# TRHPSVG_Controls.net
KiCad netlist of a schematic drawn in EAGLE
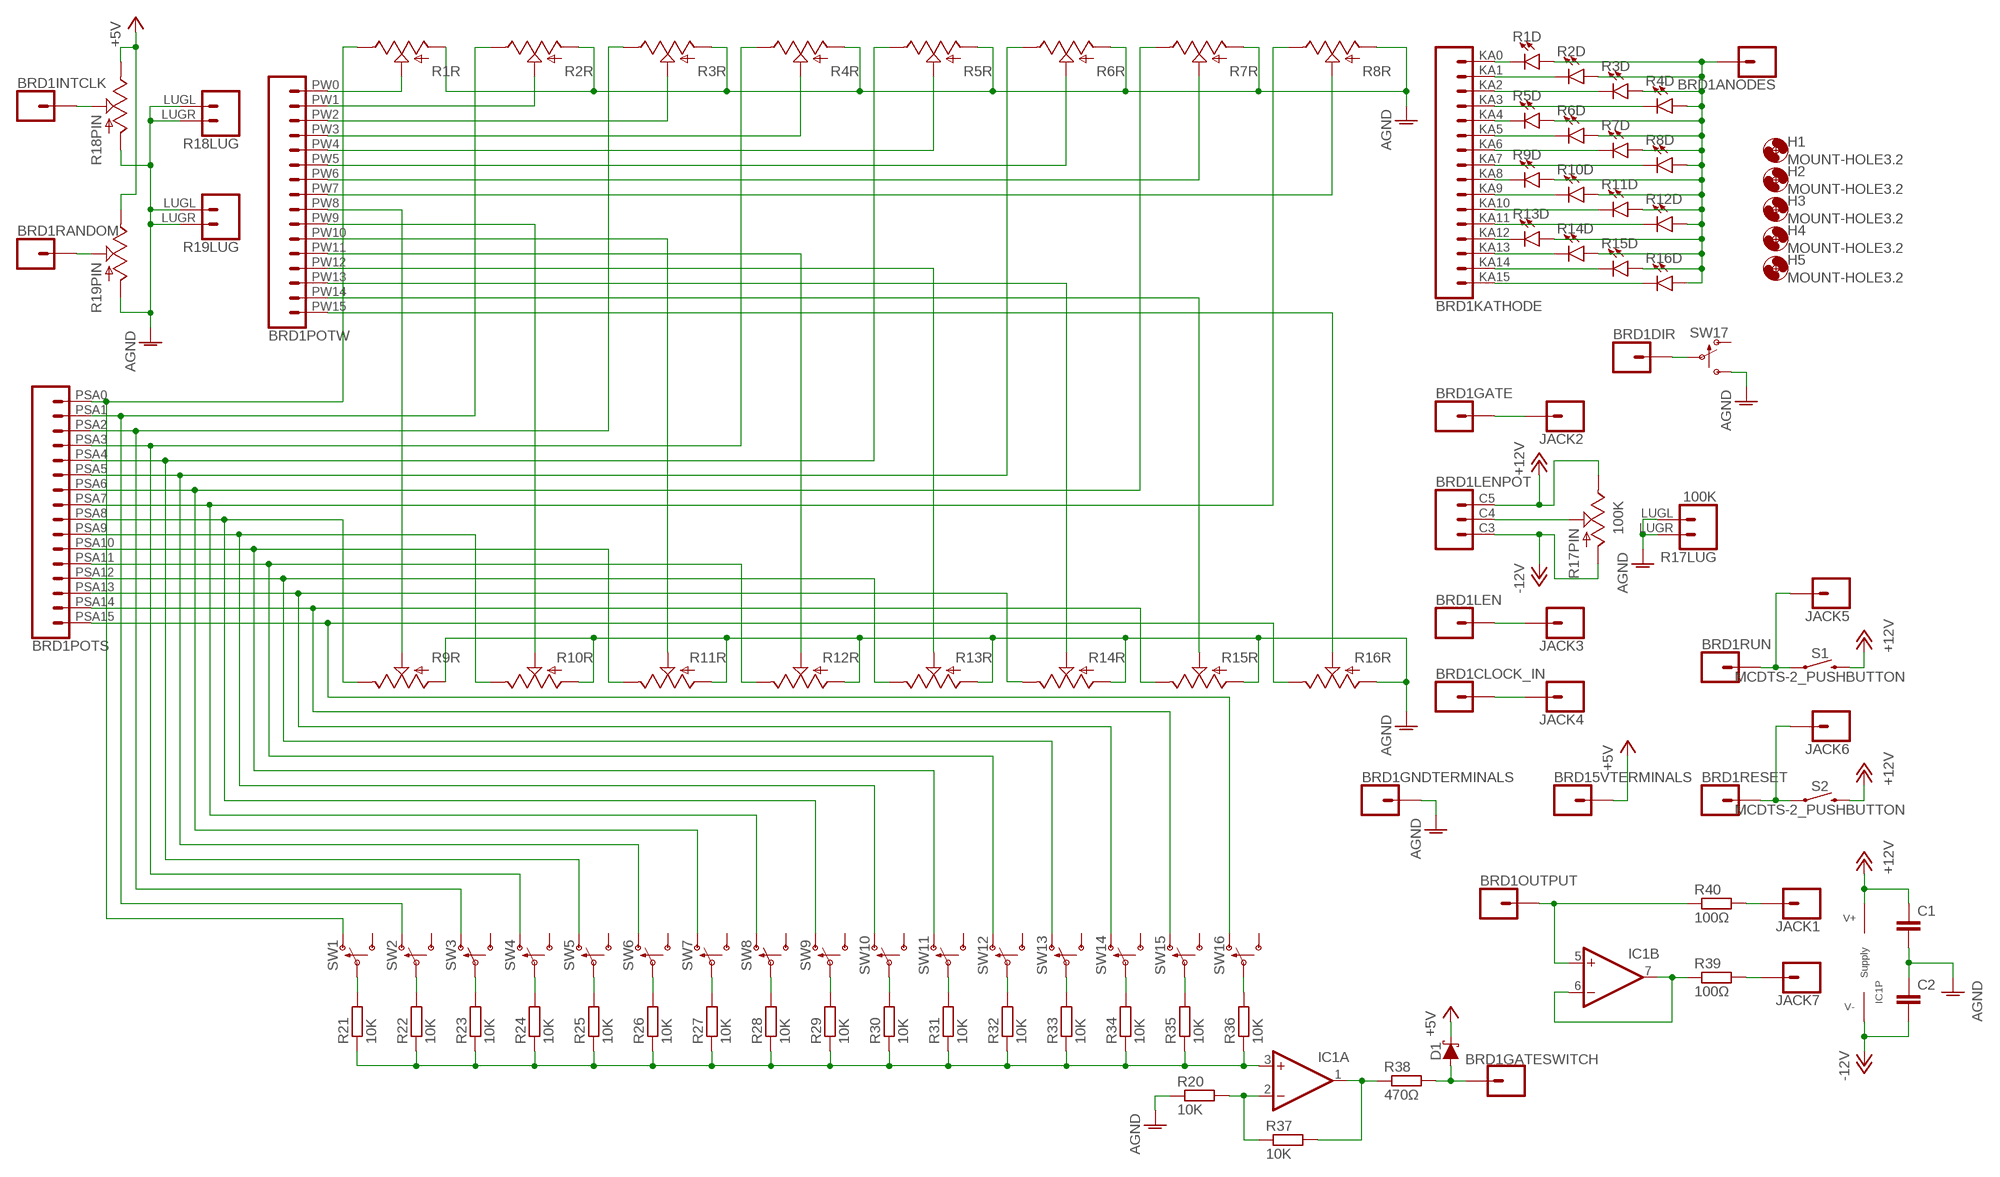
[diagram p0: schematic, sheet 1]

(export (version "E")
  (design (tool "Eeschema 10.0.6"))
  (components
    (comp (ref "BRD1")
      (value "TRHPSVG_LINK")
      (footprint "eagle-import:TRHPSVG")
      (libsource (lib "eagle-import") (part "TRHPSVG_LINK"))
    )
    (comp (ref "C1")
      (value "C-EU050-025X075")
      (footprint "eagle-import:C050-025X075")
      (libsource (lib "eagle-import") (part "C-EU050-025X075"))
    )
    (comp (ref "C2")
      (value "C-EU050-025X075")
      (footprint "eagle-import:C050-025X075")
      (libsource (lib "eagle-import") (part "C-EU050-025X075"))
    )
    (comp (ref "D1")
      (value "SCHOTTKY_DO35")
      (footprint "eagle-import:DO35-7")
      (libsource (lib "eagle-import") (part "SCHOTTKY_DO35"))
    )
    (comp (ref "H1")
      (value "MOUNT-HOLE3.2")
      (footprint "eagle-import:3,2")
      (libsource (lib "eagle-import") (part "MOUNT-HOLE3.2"))
    )
    (comp (ref "H2")
      (value "MOUNT-HOLE3.2")
      (footprint "eagle-import:3,2")
      (libsource (lib "eagle-import") (part "MOUNT-HOLE3.2"))
    )
    (comp (ref "H3")
      (value "MOUNT-HOLE3.2")
      (footprint "eagle-import:3,2")
      (libsource (lib "eagle-import") (part "MOUNT-HOLE3.2"))
    )
    (comp (ref "H4")
      (value "MOUNT-HOLE3.2")
      (footprint "eagle-import:3,2")
      (libsource (lib "eagle-import") (part "MOUNT-HOLE3.2"))
    )
    (comp (ref "H5")
      (value "MOUNT-HOLE3.2")
      (footprint "eagle-import:3,2")
      (libsource (lib "eagle-import") (part "MOUNT-HOLE3.2"))
    )
    (comp (ref "IC1")
      (value "TL0X2DIL")
      (footprint "eagle-import:DIL08")
      (libsource (lib "eagle-import") (part "TL0X2DIL"))
    )
    (comp (ref "JACK1")
      (value "1XWIREPAD")
      (footprint "eagle-import:1X01")
      (libsource (lib "eagle-import") (part "1XWIREPAD"))
    )
    (comp (ref "JACK2")
      (value "1XWIREPAD")
      (footprint "eagle-import:1X01")
      (libsource (lib "eagle-import") (part "1XWIREPAD"))
    )
    (comp (ref "JACK3")
      (value "1XWIREPAD")
      (footprint "eagle-import:1X01")
      (libsource (lib "eagle-import") (part "1XWIREPAD"))
    )
    (comp (ref "JACK4")
      (value "1XWIREPAD")
      (footprint "eagle-import:1X01")
      (libsource (lib "eagle-import") (part "1XWIREPAD"))
    )
    (comp (ref "JACK5")
      (value "1XWIREPAD")
      (footprint "eagle-import:1X01")
      (libsource (lib "eagle-import") (part "1XWIREPAD"))
    )
    (comp (ref "JACK6")
      (value "1XWIREPAD")
      (footprint "eagle-import:1X01")
      (libsource (lib "eagle-import") (part "1XWIREPAD"))
    )
    (comp (ref "JACK7")
      (value "1XWIREPAD")
      (footprint "eagle-import:1X01")
      (libsource (lib "eagle-import") (part "1XWIREPAD"))
    )
    (comp (ref "R1")
      (value "PTL30_SLIDER")
      (footprint "eagle-import:LEDSLIDER45MM")
      (libsource (lib "eagle-import") (part "PTL30_SLIDER"))
    )
    (comp (ref "R2")
      (value "PTL30_SLIDER")
      (footprint "eagle-import:LEDSLIDER45MM")
      (libsource (lib "eagle-import") (part "PTL30_SLIDER"))
    )
    (comp (ref "R3")
      (value "PTL30_SLIDER")
      (footprint "eagle-import:LEDSLIDER45MM")
      (libsource (lib "eagle-import") (part "PTL30_SLIDER"))
    )
    (comp (ref "R4")
      (value "PTL30_SLIDER")
      (footprint "eagle-import:LEDSLIDER45MM")
      (libsource (lib "eagle-import") (part "PTL30_SLIDER"))
    )
    (comp (ref "R5")
      (value "PTL30_SLIDER")
      (footprint "eagle-import:LEDSLIDER45MM")
      (libsource (lib "eagle-import") (part "PTL30_SLIDER"))
    )
    (comp (ref "R6")
      (value "PTL30_SLIDER")
      (footprint "eagle-import:LEDSLIDER45MM")
      (libsource (lib "eagle-import") (part "PTL30_SLIDER"))
    )
    (comp (ref "R7")
      (value "PTL30_SLIDER")
      (footprint "eagle-import:LEDSLIDER45MM")
      (libsource (lib "eagle-import") (part "PTL30_SLIDER"))
    )
    (comp (ref "R8")
      (value "PTL30_SLIDER")
      (footprint "eagle-import:LEDSLIDER45MM")
      (libsource (lib "eagle-import") (part "PTL30_SLIDER"))
    )
    (comp (ref "R9")
      (value "PTL30_SLIDER")
      (footprint "eagle-import:LEDSLIDER45MM")
      (libsource (lib "eagle-import") (part "PTL30_SLIDER"))
    )
    (comp (ref "R10")
      (value "PTL30_SLIDER")
      (footprint "eagle-import:LEDSLIDER45MM")
      (libsource (lib "eagle-import") (part "PTL30_SLIDER"))
    )
    (comp (ref "R11")
      (value "PTL30_SLIDER")
      (footprint "eagle-import:LEDSLIDER45MM")
      (libsource (lib "eagle-import") (part "PTL30_SLIDER"))
    )
    (comp (ref "R12")
      (value "PTL30_SLIDER")
      (footprint "eagle-import:LEDSLIDER45MM")
      (libsource (lib "eagle-import") (part "PTL30_SLIDER"))
    )
    (comp (ref "R13")
      (value "PTL30_SLIDER")
      (footprint "eagle-import:LEDSLIDER45MM")
      (libsource (lib "eagle-import") (part "PTL30_SLIDER"))
    )
    (comp (ref "R14")
      (value "PTL30_SLIDER")
      (footprint "eagle-import:LEDSLIDER45MM")
      (libsource (lib "eagle-import") (part "PTL30_SLIDER"))
    )
    (comp (ref "R15")
      (value "PTL30_SLIDER")
      (footprint "eagle-import:LEDSLIDER45MM")
      (libsource (lib "eagle-import") (part "PTL30_SLIDER"))
    )
    (comp (ref "R16")
      (value "PTL30_SLIDER")
      (footprint "eagle-import:LEDSLIDER45MM")
      (libsource (lib "eagle-import") (part "PTL30_SLIDER"))
    )
    (comp (ref "R17")
      (value "100K")
      (footprint "eagle-import:ALPHA_RV09_9MMPOT")
      (libsource (lib "eagle-import") (part "POTENTIOMETER"))
    )
    (comp (ref "R18")
      (value "POTENTIOMETER")
      (footprint "eagle-import:ALPHA_RV09_9MMPOT")
      (libsource (lib "eagle-import") (part "POTENTIOMETER"))
    )
    (comp (ref "R19")
      (value "POTENTIOMETER")
      (footprint "eagle-import:ALPHA_RV09_9MMPOT")
      (libsource (lib "eagle-import") (part "POTENTIOMETER"))
    )
    (comp (ref "R20")
      (value "10K")
      (footprint "eagle-import:0207_10")
      (libsource (lib "eagle-import") (part "R-EU_0207/10"))
    )
    (comp (ref "R21")
      (value "10K")
      (footprint "eagle-import:0207_10")
      (libsource (lib "eagle-import") (part "R-EU_0207/10"))
    )
    (comp (ref "R22")
      (value "10K")
      (footprint "eagle-import:0207_10")
      (libsource (lib "eagle-import") (part "R-EU_0207/10"))
    )
    (comp (ref "R23")
      (value "10K")
      (footprint "eagle-import:0207_10")
      (libsource (lib "eagle-import") (part "R-EU_0207/10"))
    )
    (comp (ref "R24")
      (value "10K")
      (footprint "eagle-import:0207_10")
      (libsource (lib "eagle-import") (part "R-EU_0207/10"))
    )
    (comp (ref "R25")
      (value "10K")
      (footprint "eagle-import:0207_10")
      (libsource (lib "eagle-import") (part "R-EU_0207/10"))
    )
    (comp (ref "R26")
      (value "10K")
      (footprint "eagle-import:0207_10")
      (libsource (lib "eagle-import") (part "R-EU_0207/10"))
    )
    (comp (ref "R27")
      (value "10K")
      (footprint "eagle-import:0207_10")
      (libsource (lib "eagle-import") (part "R-EU_0207/10"))
    )
    (comp (ref "R28")
      (value "10K")
      (footprint "eagle-import:0207_10")
      (libsource (lib "eagle-import") (part "R-EU_0207/10"))
    )
    (comp (ref "R29")
      (value "10K")
      (footprint "eagle-import:0207_10")
      (libsource (lib "eagle-import") (part "R-EU_0207/10"))
    )
    (comp (ref "R30")
      (value "10K")
      (footprint "eagle-import:0207_10")
      (libsource (lib "eagle-import") (part "R-EU_0207/10"))
    )
    (comp (ref "R31")
      (value "10K")
      (footprint "eagle-import:0207_10")
      (libsource (lib "eagle-import") (part "R-EU_0207/10"))
    )
    (comp (ref "R32")
      (value "10K")
      (footprint "eagle-import:0207_10")
      (libsource (lib "eagle-import") (part "R-EU_0207/10"))
    )
    (comp (ref "R33")
      (value "10K")
      (footprint "eagle-import:0207_10")
      (libsource (lib "eagle-import") (part "R-EU_0207/10"))
    )
    (comp (ref "R34")
      (value "10K")
      (footprint "eagle-import:0207_10")
      (libsource (lib "eagle-import") (part "R-EU_0207/10"))
    )
    (comp (ref "R35")
      (value "10K")
      (footprint "eagle-import:0207_10")
      (libsource (lib "eagle-import") (part "R-EU_0207/10"))
    )
    (comp (ref "R36")
      (value "10K")
      (footprint "eagle-import:0207_10")
      (libsource (lib "eagle-import") (part "R-EU_0207/10"))
    )
    (comp (ref "R37")
      (value "10K")
      (footprint "eagle-import:0207_10")
      (libsource (lib "eagle-import") (part "R-EU_0207/10"))
    )
    (comp (ref "R38")
      (value "470Ω")
      (footprint "eagle-import:0207_10")
      (libsource (lib "eagle-import") (part "R-EU_0207/10"))
    )
    (comp (ref "R39")
      (value "100Ω")
      (footprint "eagle-import:0207_10")
      (libsource (lib "eagle-import") (part "R-EU_0207/10"))
    )
    (comp (ref "R40")
      (value "100Ω")
      (footprint "eagle-import:0207_10")
      (libsource (lib "eagle-import") (part "R-EU_0207/10"))
    )
    (comp (ref "S1")
      (value "MCDTS-2_PUSHBUTTON")
      (footprint "eagle-import:MCDTS-2_PUSHBUTTON")
      (libsource (lib "eagle-import") (part "MCDTS-2_PUSHBUTTON"))
    )
    (comp (ref "S2")
      (value "MCDTS-2_PUSHBUTTON")
      (footprint "eagle-import:MCDTS-2_PUSHBUTTON")
      (libsource (lib "eagle-import") (part "MCDTS-2_PUSHBUTTON"))
    )
    (comp (ref "SW1")
      (value "SPDT_SWITCHDW1")
      (footprint "eagle-import:MICRODPDT-DW1")
      (libsource (lib "eagle-import") (part "SPDT_SWITCHDW1"))
    )
    (comp (ref "SW2")
      (value "SPDT_SWITCHDW1")
      (footprint "eagle-import:MICRODPDT-DW1")
      (libsource (lib "eagle-import") (part "SPDT_SWITCHDW1"))
    )
    (comp (ref "SW3")
      (value "SPDT_SWITCHDW1")
      (footprint "eagle-import:MICRODPDT-DW1")
      (libsource (lib "eagle-import") (part "SPDT_SWITCHDW1"))
    )
    (comp (ref "SW4")
      (value "SPDT_SWITCHDW1")
      (footprint "eagle-import:MICRODPDT-DW1")
      (libsource (lib "eagle-import") (part "SPDT_SWITCHDW1"))
    )
    (comp (ref "SW5")
      (value "SPDT_SWITCHDW1")
      (footprint "eagle-import:MICRODPDT-DW1")
      (libsource (lib "eagle-import") (part "SPDT_SWITCHDW1"))
    )
    (comp (ref "SW6")
      (value "SPDT_SWITCHDW1")
      (footprint "eagle-import:MICRODPDT-DW1")
      (libsource (lib "eagle-import") (part "SPDT_SWITCHDW1"))
    )
    (comp (ref "SW7")
      (value "SPDT_SWITCHDW1")
      (footprint "eagle-import:MICRODPDT-DW1")
      (libsource (lib "eagle-import") (part "SPDT_SWITCHDW1"))
    )
    (comp (ref "SW8")
      (value "SPDT_SWITCHDW1")
      (footprint "eagle-import:MICRODPDT-DW1")
      (libsource (lib "eagle-import") (part "SPDT_SWITCHDW1"))
    )
    (comp (ref "SW9")
      (value "SPDT_SWITCHDW1")
      (footprint "eagle-import:MICRODPDT-DW1")
      (libsource (lib "eagle-import") (part "SPDT_SWITCHDW1"))
    )
    (comp (ref "SW10")
      (value "SPDT_SWITCHDW1")
      (footprint "eagle-import:MICRODPDT-DW1")
      (libsource (lib "eagle-import") (part "SPDT_SWITCHDW1"))
    )
    (comp (ref "SW11")
      (value "SPDT_SWITCHDW1")
      (footprint "eagle-import:MICRODPDT-DW1")
      (libsource (lib "eagle-import") (part "SPDT_SWITCHDW1"))
    )
    (comp (ref "SW12")
      (value "SPDT_SWITCHDW1")
      (footprint "eagle-import:MICRODPDT-DW1")
      (libsource (lib "eagle-import") (part "SPDT_SWITCHDW1"))
    )
    (comp (ref "SW13")
      (value "SPDT_SWITCHDW1")
      (footprint "eagle-import:MICRODPDT-DW1")
      (libsource (lib "eagle-import") (part "SPDT_SWITCHDW1"))
    )
    (comp (ref "SW14")
      (value "SPDT_SWITCHDW1")
      (footprint "eagle-import:MICRODPDT-DW1")
      (libsource (lib "eagle-import") (part "SPDT_SWITCHDW1"))
    )
    (comp (ref "SW15")
      (value "SPDT_SWITCHDW1")
      (footprint "eagle-import:MICRODPDT-DW1")
      (libsource (lib "eagle-import") (part "SPDT_SWITCHDW1"))
    )
    (comp (ref "SW16")
      (value "SPDT_SWITCHDW1")
      (footprint "eagle-import:MICRODPDT-DW1")
      (libsource (lib "eagle-import") (part "SPDT_SWITCHDW1"))
    )
    (comp (ref "SW17")
      (value "SPDT_SWITCHDW1")
      (footprint "eagle-import:MICRODPDT-DW1")
      (libsource (lib "eagle-import") (part "SPDT_SWITCHDW1"))
    )
  )
  (nets
    (net (code "1") (name "+5V") (class "Default")
      (node (ref "BRD1") (pin "C13") (pinfunction "1_C13") (pintype "passive"))
      (node (ref "BRD1") (pin "C14") (pinfunction "1_C14") (pintype "passive"))
      (node (ref "BRD1") (pin "C15") (pinfunction "1_C15") (pintype "passive"))
      (node (ref "D1") (pin "C") (pinfunction "C_C") (pintype "passive"))
      (node (ref "R18") (pin "C3") (pinfunction "B_C3") (pintype "passive"))
      (node (ref "R19") (pin "C3") (pinfunction "B_C3") (pintype "passive"))
    )
    (net (code "2") (name "+12V") (class "Default")
      (node (ref "BRD1") (pin "C5") (pinfunction "3_C5") (pintype "passive"))
      (node (ref "C1") (pin "1") (pinfunction "1_1") (pintype "passive"))
      (node (ref "IC1") (pin "8") (pinfunction "V+_8") (pintype "bidirectional"))
      (node (ref "R17") (pin "C3") (pinfunction "B_C3") (pintype "passive"))
      (node (ref "S1") (pin "P$3") (pinfunction "2_P$3") (pintype "passive"))
      (node (ref "S1") (pin "P$4") (pinfunction "2_P$4") (pintype "passive"))
      (node (ref "S2") (pin "P$3") (pinfunction "2_P$3") (pintype "passive"))
      (node (ref "S2") (pin "P$4") (pinfunction "2_P$4") (pintype "passive"))
    )
    (net (code "3") (name "-12V") (class "Default")
      (node (ref "BRD1") (pin "C3") (pinfunction "1_C3") (pintype "passive"))
      (node (ref "C2") (pin "2") (pinfunction "2_2") (pintype "passive"))
      (node (ref "IC1") (pin "4") (pinfunction "V-_4") (pintype "bidirectional"))
      (node (ref "R17") (pin "C1") (pinfunction "A_C1") (pintype "passive"))
    )
    (net (code "4") (name "AGND") (class "Default")
      (node (ref "BRD1") (pin "C16") (pinfunction "1_C16") (pintype "passive"))
      (node (ref "BRD1") (pin "C17") (pinfunction "1_C17") (pintype "passive"))
      (node (ref "BRD1") (pin "C18") (pinfunction "1_C18") (pintype "passive"))
      (node (ref "BRD1") (pin "GNDTA0") (pinfunction "1_GNDTA0") (pintype "passive"))
      (node (ref "BRD1") (pin "GNDTA1") (pinfunction "1_GNDTA1") (pintype "passive"))
      (node (ref "BRD1") (pin "GNDTA10") (pinfunction "1_GNDTA10") (pintype "passive"))
      (node (ref "BRD1") (pin "GNDTA11") (pinfunction "1_GNDTA11") (pintype "passive"))
      (node (ref "BRD1") (pin "GNDTA12") (pinfunction "1_GNDTA12") (pintype "passive"))
      (node (ref "BRD1") (pin "GNDTA13") (pinfunction "1_GNDTA13") (pintype "passive"))
      (node (ref "BRD1") (pin "GNDTA14") (pinfunction "1_GNDTA14") (pintype "passive"))
      (node (ref "BRD1") (pin "GNDTA15") (pinfunction "1_GNDTA15") (pintype "passive"))
      (node (ref "BRD1") (pin "GNDTA2") (pinfunction "1_GNDTA2") (pintype "passive"))
      (node (ref "BRD1") (pin "GNDTA3") (pinfunction "1_GNDTA3") (pintype "passive"))
      (node (ref "BRD1") (pin "GNDTA4") (pinfunction "1_GNDTA4") (pintype "passive"))
      (node (ref "BRD1") (pin "GNDTA5") (pinfunction "1_GNDTA5") (pintype "passive"))
      (node (ref "BRD1") (pin "GNDTA6") (pinfunction "1_GNDTA6") (pintype "passive"))
      (node (ref "BRD1") (pin "GNDTA7") (pinfunction "1_GNDTA7") (pintype "passive"))
      (node (ref "BRD1") (pin "GNDTA8") (pinfunction "1_GNDTA8") (pintype "passive"))
      (node (ref "BRD1") (pin "GNDTA9") (pinfunction "1_GNDTA9") (pintype "passive"))
      (node (ref "C1") (pin "2") (pinfunction "2_2") (pintype "passive"))
      (node (ref "C2") (pin "1") (pinfunction "1_1") (pintype "passive"))
      (node (ref "R1") (pin "S1") (pinfunction "A_S1") (pintype "passive"))
      (node (ref "R10") (pin "S1") (pinfunction "A_S1") (pintype "passive"))
      (node (ref "R11") (pin "S1") (pinfunction "A_S1") (pintype "passive"))
      (node (ref "R12") (pin "S1") (pinfunction "A_S1") (pintype "passive"))
      (node (ref "R13") (pin "S1") (pinfunction "A_S1") (pintype "passive"))
      (node (ref "R14") (pin "S1") (pinfunction "A_S1") (pintype "passive"))
      (node (ref "R15") (pin "S1") (pinfunction "A_S1") (pintype "passive"))
      (node (ref "R16") (pin "S1") (pinfunction "A_S1") (pintype "passive"))
      (node (ref "R17") (pin "LUGL") (pinfunction "1_LUGL") (pintype "passive"))
      (node (ref "R17") (pin "LUGR") (pinfunction "2_LUGR") (pintype "passive"))
      (node (ref "R18") (pin "C1") (pinfunction "A_C1") (pintype "passive"))
      (node (ref "R18") (pin "LUGL") (pinfunction "1_LUGL") (pintype "passive"))
      (node (ref "R18") (pin "LUGR") (pinfunction "2_LUGR") (pintype "passive"))
      (node (ref "R19") (pin "C1") (pinfunction "A_C1") (pintype "passive"))
      (node (ref "R19") (pin "LUGL") (pinfunction "1_LUGL") (pintype "passive"))
      (node (ref "R19") (pin "LUGR") (pinfunction "2_LUGR") (pintype "passive"))
      (node (ref "R2") (pin "S1") (pinfunction "A_S1") (pintype "passive"))
      (node (ref "R20") (pin "1") (pinfunction "1_1") (pintype "passive"))
      (node (ref "R3") (pin "S1") (pinfunction "A_S1") (pintype "passive"))
      (node (ref "R4") (pin "S1") (pinfunction "A_S1") (pintype "passive"))
      (node (ref "R5") (pin "S1") (pinfunction "A_S1") (pintype "passive"))
      (node (ref "R6") (pin "S1") (pinfunction "A_S1") (pintype "passive"))
      (node (ref "R7") (pin "S1") (pinfunction "A_S1") (pintype "passive"))
      (node (ref "R8") (pin "S1") (pinfunction "A_S1") (pintype "passive"))
      (node (ref "R9") (pin "S1") (pinfunction "A_S1") (pintype "passive"))
      (node (ref "SW17") (pin "C3") (pinfunction "S_C3") (pintype "passive"))
    )
    (net (code "5") (name "Net-(BRD1C-1)") (class "Default")
      (node (ref "BRD1") (pin "C6") (pinfunction "1_C6") (pintype "passive"))
      (node (ref "JACK4") (pin "1") (pinfunction "1_1") (pintype "passive"))
    )
    (net (code "6") (name "Net-(BRD1D-1)") (class "Default")
      (node (ref "BRD1") (pin "C11") (pinfunction "1_C11") (pintype "passive"))
      (node (ref "SW17") (pin "C2") (pinfunction "P_C2") (pintype "passive"))
    )
    (net (code "7") (name "Net-(BRD1E-1)") (class "Default")
      (node (ref "BRD1") (pin "C1") (pinfunction "1_C1") (pintype "passive"))
      (node (ref "JACK2") (pin "1") (pinfunction "1_1") (pintype "passive"))
    )
    (net (code "8") (name "Net-(BRD1F-1)") (class "Default")
      (node (ref "BRD1") (pin "C12") (pinfunction "1_C12") (pintype "passive"))
      (node (ref "D1") (pin "A") (pinfunction "A_A") (pintype "passive"))
      (node (ref "R38") (pin "2") (pinfunction "2_2") (pintype "passive"))
    )
    (net (code "9") (name "Net-(BRD1H-1)") (class "Default")
      (node (ref "BRD1") (pin "C9") (pinfunction "1_C9") (pintype "passive"))
      (node (ref "R18") (pin "C2") (pinfunction "W_C2") (pintype "passive"))
    )
    (net (code "10") (name "Net-(BRD1I-1)") (class "Default")
      (node (ref "BRD1") (pin "KA0") (pinfunction "1_KA0") (pintype "passive"))
      (node (ref "R1") (pin "SE") (pinfunction "C_SE") (pintype "passive"))
    )
    (net (code "11") (name "Net-(BRD1I-2)") (class "Default")
      (node (ref "BRD1") (pin "KA1") (pinfunction "2_KA1") (pintype "passive"))
      (node (ref "R2") (pin "SE") (pinfunction "C_SE") (pintype "passive"))
    )
    (net (code "12") (name "Net-(BRD1I-3)") (class "Default")
      (node (ref "BRD1") (pin "KA2") (pinfunction "3_KA2") (pintype "passive"))
      (node (ref "R3") (pin "SE") (pinfunction "C_SE") (pintype "passive"))
    )
    (net (code "13") (name "Net-(BRD1I-4)") (class "Default")
      (node (ref "BRD1") (pin "KA3") (pinfunction "4_KA3") (pintype "passive"))
      (node (ref "R4") (pin "SE") (pinfunction "C_SE") (pintype "passive"))
    )
    (net (code "14") (name "Net-(BRD1I-5)") (class "Default")
      (node (ref "BRD1") (pin "KA4") (pinfunction "5_KA4") (pintype "passive"))
      (node (ref "R5") (pin "SE") (pinfunction "C_SE") (pintype "passive"))
    )
    (net (code "15") (name "Net-(BRD1I-6)") (class "Default")
      (node (ref "BRD1") (pin "KA5") (pinfunction "6_KA5") (pintype "passive"))
      (node (ref "R6") (pin "SE") (pinfunction "C_SE") (pintype "passive"))
    )
    (net (code "16") (name "Net-(BRD1I-7)") (class "Default")
      (node (ref "BRD1") (pin "KA6") (pinfunction "7_KA6") (pintype "passive"))
      (node (ref "R7") (pin "SE") (pinfunction "C_SE") (pintype "passive"))
    )
    (net (code "17") (name "Net-(BRD1I-8)") (class "Default")
      (node (ref "BRD1") (pin "KA7") (pinfunction "8_KA7") (pintype "passive"))
      (node (ref "R8") (pin "SE") (pinfunction "C_SE") (pintype "passive"))
    )
    (net (code "18") (name "Net-(BRD1I-9)") (class "Default")
      (node (ref "BRD1") (pin "KA8") (pinfunction "9_KA8") (pintype "passive"))
      (node (ref "R9") (pin "SE") (pinfunction "C_SE") (pintype "passive"))
    )
    (net (code "19") (name "Net-(BRD1I-10)") (class "Default")
      (node (ref "BRD1") (pin "KA9") (pinfunction "10_KA9") (pintype "passive"))
      (node (ref "R10") (pin "SE") (pinfunction "C_SE") (pintype "passive"))
    )
    (net (code "20") (name "Net-(BRD1I-11)") (class "Default")
      (node (ref "BRD1") (pin "KA10") (pinfunction "11_KA10") (pintype "passive"))
      (node (ref "R11") (pin "SE") (pinfunction "C_SE") (pintype "passive"))
    )
    (net (code "21") (name "Net-(BRD1I-12)") (class "Default")
      (node (ref "BRD1") (pin "KA11") (pinfunction "12_KA11") (pintype "passive"))
      (node (ref "R12") (pin "SE") (pinfunction "C_SE") (pintype "passive"))
    )
    (net (code "22") (name "Net-(BRD1I-13)") (class "Default")
      (node (ref "BRD1") (pin "KA12") (pinfunction "13_KA12") (pintype "passive"))
      (node (ref "R13") (pin "SE") (pinfunction "C_SE") (pintype "passive"))
    )
    (net (code "23") (name "Net-(BRD1I-14)") (class "Default")
      (node (ref "BRD1") (pin "KA13") (pinfunction "14_KA13") (pintype "passive"))
      (node (ref "R14") (pin "SE") (pinfunction "C_SE") (pintype "passive"))
    )
    (net (code "24") (name "Net-(BRD1I-15)") (class "Default")
      (node (ref "BRD1") (pin "KA14") (pinfunction "15_KA14") (pintype "passive"))
      (node (ref "R15") (pin "SE") (pinfunction "C_SE") (pintype "passive"))
    )
    (net (code "25") (name "Net-(BRD1I-16)") (class "Default")
      (node (ref "BRD1") (pin "KA15") (pinfunction "16_KA15") (pintype "passive"))
      (node (ref "R16") (pin "SE") (pinfunction "C_SE") (pintype "passive"))
    )
    (net (code "26") (name "Net-(BRD1J-1)") (class "Default")
      (node (ref "BRD1") (pin "C2") (pinfunction "1_C2") (pintype "passive"))
      (node (ref "JACK3") (pin "1") (pinfunction "1_1") (pintype "passive"))
    )
    (net (code "27") (name "Net-(BRD1K-2)") (class "Default")
      (node (ref "BRD1") (pin "C4") (pinfunction "2_C4") (pintype "passive"))
      (node (ref "R17") (pin "C2") (pinfunction "W_C2") (pintype "passive"))
    )
    (net (code "28") (name "Net-(BRD1L-1)") (class "Default")
      (node (ref "BRD1") (pin "C0") (pinfunction "1_C0") (pintype "passive"))
      (node (ref "IC1") (pin "5") (pinfunction "+IN_5") (pintype "input"))
      (node (ref "R40") (pin "1") (pinfunction "1_1") (pintype "passive"))
    )
    (net (code "29") (name "Net-(BRD1M-1)") (class "Default")
      (node (ref "BRD1") (pin "PSA0") (pinfunction "1_PSA0") (pintype "passive"))
      (node (ref "R1") (pin "S3") (pinfunction "B_S3") (pintype "passive"))
      (node (ref "SW1") (pin "C1") (pinfunction "O_C1") (pintype "passive"))
    )
    (net (code "30") (name "Net-(BRD1M-2)") (class "Default")
      (node (ref "BRD1") (pin "PSA1") (pinfunction "2_PSA1") (pintype "passive"))
      (node (ref "R2") (pin "S3") (pinfunction "B_S3") (pintype "passive"))
      (node (ref "SW2") (pin "C1") (pinfunction "O_C1") (pintype "passive"))
    )
    (net (code "31") (name "Net-(BRD1M-3)") (class "Default")
      (node (ref "BRD1") (pin "PSA2") (pinfunction "3_PSA2") (pintype "passive"))
      (node (ref "R3") (pin "S3") (pinfunction "B_S3") (pintype "passive"))
      (node (ref "SW3") (pin "C1") (pinfunction "O_C1") (pintype "passive"))
    )
    (net (code "32") (name "Net-(BRD1M-4)") (class "Default")
      (node (ref "BRD1") (pin "PSA3") (pinfunction "4_PSA3") (pintype "passive"))
      (node (ref "R4") (pin "S3") (pinfunction "B_S3") (pintype "passive"))
      (node (ref "SW4") (pin "C1") (pinfunction "O_C1") (pintype "passive"))
    )
    (net (code "33") (name "Net-(BRD1M-5)") (class "Default")
      (node (ref "BRD1") (pin "PSA4") (pinfunction "5_PSA4") (pintype "passive"))
      (node (ref "R5") (pin "S3") (pinfunction "B_S3") (pintype "passive"))
      (node (ref "SW5") (pin "C1") (pinfunction "O_C1") (pintype "passive"))
    )
    (net (code "34") (name "Net-(BRD1M-6)") (class "Default")
      (node (ref "BRD1") (pin "PSA5") (pinfunction "6_PSA5") (pintype "passive"))
      (node (ref "R6") (pin "S3") (pinfunction "B_S3") (pintype "passive"))
      (node (ref "SW6") (pin "C1") (pinfunction "O_C1") (pintype "passive"))
    )
    (net (code "35") (name "Net-(BRD1M-7)") (class "Default")
      (node (ref "BRD1") (pin "PSA6") (pinfunction "7_PSA6") (pintype "passive"))
      (node (ref "R7") (pin "S3") (pinfunction "B_S3") (pintype "passive"))
      (node (ref "SW7") (pin "C1") (pinfunction "O_C1") (pintype "passive"))
    )
    (net (code "36") (name "Net-(BRD1M-8)") (class "Default")
      (node (ref "BRD1") (pin "PSA7") (pinfunction "8_PSA7") (pintype "passive"))
      (node (ref "R8") (pin "S3") (pinfunction "B_S3") (pintype "passive"))
      (node (ref "SW8") (pin "C1") (pinfunction "O_C1") (pintype "passive"))
    )
    (net (code "37") (name "Net-(BRD1M-9)") (class "Default")
      (node (ref "BRD1") (pin "PSA8") (pinfunction "9_PSA8") (pintype "passive"))
      (node (ref "R9") (pin "S3") (pinfunction "B_S3") (pintype "passive"))
      (node (ref "SW9") (pin "C1") (pinfunction "O_C1") (pintype "passive"))
    )
    (net (code "38") (name "Net-(BRD1M-10)") (class "Default")
      (node (ref "BRD1") (pin "PSA9") (pinfunction "10_PSA9") (pintype "passive"))
      (node (ref "R10") (pin "S3") (pinfunction "B_S3") (pintype "passive"))
      (node (ref "SW10") (pin "C1") (pinfunction "O_C1") (pintype "passive"))
    )
    (net (code "39") (name "Net-(BRD1M-11)") (class "Default")
      (node (ref "BRD1") (pin "PSA10") (pinfunction "11_PSA10") (pintype "passive"))
      (node (ref "R11") (pin "S3") (pinfunction "B_S3") (pintype "passive"))
      (node (ref "SW11") (pin "C1") (pinfunction "O_C1") (pintype "passive"))
    )
    (net (code "40") (name "Net-(BRD1M-12)") (class "Default")
      (node (ref "BRD1") (pin "PSA11") (pinfunction "12_PSA11") (pintype "passive"))
      (node (ref "R12") (pin "S3") (pinfunction "B_S3") (pintype "passive"))
      (node (ref "SW12") (pin "C1") (pinfunction "O_C1") (pintype "passive"))
    )
    (net (code "41") (name "Net-(BRD1M-13)") (class "Default")
      (node (ref "BRD1") (pin "PSA12") (pinfunction "13_PSA12") (pintype "passive"))
      (node (ref "R13") (pin "S3") (pinfunction "B_S3") (pintype "passive"))
      (node (ref "SW13") (pin "C1") (pinfunction "O_C1") (pintype "passive"))
    )
    (net (code "42") (name "Net-(BRD1M-14)") (class "Default")
      (node (ref "BRD1") (pin "PSA13") (pinfunction "14_PSA13") (pintype "passive"))
      (node (ref "R14") (pin "S3") (pinfunction "B_S3") (pintype "passive"))
      (node (ref "SW14") (pin "C1") (pinfunction "O_C1") (pintype "passive"))
    )
    (net (code "43") (name "Net-(BRD1M-15)") (class "Default")
      (node (ref "BRD1") (pin "PSA14") (pinfunction "15_PSA14") (pintype "passive"))
      (node (ref "R15") (pin "S3") (pinfunction "B_S3") (pintype "passive"))
      (node (ref "SW15") (pin "C1") (pinfunction "O_C1") (pintype "passive"))
    )
    (net (code "44") (name "Net-(BRD1M-16)") (class "Default")
      (node (ref "BRD1") (pin "PSA15") (pinfunction "16_PSA15") (pintype "passive"))
      (node (ref "R16") (pin "S3") (pinfunction "B_S3") (pintype "passive"))
      (node (ref "SW16") (pin "C1") (pinfunction "O_C1") (pintype "passive"))
    )
    (net (code "45") (name "Net-(BRD1N-1)") (class "Default")
      (node (ref "BRD1") (pin "PW0") (pinfunction "1_PW0") (pintype "passive"))
      (node (ref "R1") (pin "S2") (pinfunction "W_S2") (pintype "passive"))
    )
    (net (code "46") (name "Net-(BRD1N-2)") (class "Default")
      (node (ref "BRD1") (pin "PW1") (pinfunction "2_PW1") (pintype "passive"))
      (node (ref "R2") (pin "S2") (pinfunction "W_S2") (pintype "passive"))
    )
    (net (code "47") (name "Net-(BRD1N-3)") (class "Default")
      (node (ref "BRD1") (pin "PW2") (pinfunction "3_PW2") (pintype "passive"))
      (node (ref "R3") (pin "S2") (pinfunction "W_S2") (pintype "passive"))
    )
    (net (code "48") (name "Net-(BRD1N-4)") (class "Default")
      (node (ref "BRD1") (pin "PW3") (pinfunction "4_PW3") (pintype "passive"))
      (node (ref "R4") (pin "S2") (pinfunction "W_S2") (pintype "passive"))
    )
    (net (code "49") (name "Net-(BRD1N-5)") (class "Default")
      (node (ref "BRD1") (pin "PW4") (pinfunction "5_PW4") (pintype "passive"))
      (node (ref "R5") (pin "S2") (pinfunction "W_S2") (pintype "passive"))
    )
    (net (code "50") (name "Net-(BRD1N-6)") (class "Default")
      (node (ref "BRD1") (pin "PW5") (pinfunction "6_PW5") (pintype "passive"))
      (node (ref "R6") (pin "S2") (pinfunction "W_S2") (pintype "passive"))
    )
    (net (code "51") (name "Net-(BRD1N-7)") (class "Default")
      (node (ref "BRD1") (pin "PW6") (pinfunction "7_PW6") (pintype "passive"))
      (node (ref "R7") (pin "S2") (pinfunction "W_S2") (pintype "passive"))
    )
    (net (code "52") (name "Net-(BRD1N-8)") (class "Default")
      (node (ref "BRD1") (pin "PW7") (pinfunction "8_PW7") (pintype "passive"))
      (node (ref "R8") (pin "S2") (pinfunction "W_S2") (pintype "passive"))
    )
    (net (code "53") (name "Net-(BRD1N-9)") (class "Default")
      (node (ref "BRD1") (pin "PW8") (pinfunction "9_PW8") (pintype "passive"))
      (node (ref "R9") (pin "S2") (pinfunction "W_S2") (pintype "passive"))
    )
    (net (code "54") (name "Net-(BRD1N-10)") (class "Default")
      (node (ref "BRD1") (pin "PW9") (pinfunction "10_PW9") (pintype "passive"))
      (node (ref "R10") (pin "S2") (pinfunction "W_S2") (pintype "passive"))
    )
    (net (code "55") (name "Net-(BRD1N-11)") (class "Default")
      (node (ref "BRD1") (pin "PW10") (pinfunction "11_PW10") (pintype "passive"))
      (node (ref "R11") (pin "S2") (pinfunction "W_S2") (pintype "passive"))
    )
    (net (code "56") (name "Net-(BRD1N-12)") (class "Default")
      (node (ref "BRD1") (pin "PW11") (pinfunction "12_PW11") (pintype "passive"))
      (node (ref "R12") (pin "S2") (pinfunction "W_S2") (pintype "passive"))
    )
    (net (code "57") (name "Net-(BRD1N-13)") (class "Default")
      (node (ref "BRD1") (pin "PW12") (pinfunction "13_PW12") (pintype "passive"))
      (node (ref "R13") (pin "S2") (pinfunction "W_S2") (pintype "passive"))
    )
    (net (code "58") (name "Net-(BRD1N-14)") (class "Default")
      (node (ref "BRD1") (pin "PW13") (pinfunction "14_PW13") (pintype "passive"))
      (node (ref "R14") (pin "S2") (pinfunction "W_S2") (pintype "passive"))
    )
    (net (code "59") (name "Net-(BRD1N-15)") (class "Default")
      (node (ref "BRD1") (pin "PW14") (pinfunction "15_PW14") (pintype "passive"))
      (node (ref "R15") (pin "S2") (pinfunction "W_S2") (pintype "passive"))
    )
    (net (code "60") (name "Net-(BRD1N-16)") (class "Default")
      (node (ref "BRD1") (pin "PW15") (pinfunction "16_PW15") (pintype "passive"))
      (node (ref "R16") (pin "S2") (pinfunction "W_S2") (pintype "passive"))
    )
    (net (code "61") (name "Net-(BRD1O-1)") (class "Default")
      (node (ref "BRD1") (pin "C10") (pinfunction "1_C10") (pintype "passive"))
      (node (ref "R19") (pin "C2") (pinfunction "W_C2") (pintype "passive"))
    )
    (net (code "62") (name "Net-(BRD1P-1)") (class "Default")
      (node (ref "BRD1") (pin "C8") (pinfunction "1_C8") (pintype "passive"))
      (node (ref "JACK6") (pin "1") (pinfunction "1_1") (pintype "passive"))
      (node (ref "S2") (pin "P$1") (pinfunction "1_P$1") (pintype "passive"))
      (node (ref "S2") (pin "P$2") (pinfunction "1_P$2") (pintype "passive"))
    )
    (net (code "63") (name "Net-(BRD1Q-1)") (class "Default")
      (node (ref "BRD1") (pin "C7") (pinfunction "1_C7") (pintype "passive"))
      (node (ref "JACK5") (pin "1") (pinfunction "1_1") (pintype "passive"))
      (node (ref "S1") (pin "P$1") (pinfunction "1_P$1") (pintype "passive"))
      (node (ref "S1") (pin "P$2") (pinfunction "1_P$2") (pintype "passive"))
    )
    (net (code "64") (name "Net-(IC1A-+IN)") (class "Default")
      (node (ref "IC1") (pin "3") (pinfunction "+IN_3") (pintype "input"))
      (node (ref "R21") (pin "1") (pinfunction "1_1") (pintype "passive"))
      (node (ref "R22") (pin "1") (pinfunction "1_1") (pintype "passive"))
      (node (ref "R23") (pin "1") (pinfunction "1_1") (pintype "passive"))
      (node (ref "R24") (pin "1") (pinfunction "1_1") (pintype "passive"))
      (node (ref "R25") (pin "1") (pinfunction "1_1") (pintype "passive"))
      (node (ref "R26") (pin "1") (pinfunction "1_1") (pintype "passive"))
      (node (ref "R27") (pin "1") (pinfunction "1_1") (pintype "passive"))
      (node (ref "R28") (pin "1") (pinfunction "1_1") (pintype "passive"))
      (node (ref "R29") (pin "1") (pinfunction "1_1") (pintype "passive"))
      (node (ref "R30") (pin "1") (pinfunction "1_1") (pintype "passive"))
      (node (ref "R31") (pin "1") (pinfunction "1_1") (pintype "passive"))
      (node (ref "R32") (pin "1") (pinfunction "1_1") (pintype "passive"))
      (node (ref "R33") (pin "1") (pinfunction "1_1") (pintype "passive"))
      (node (ref "R34") (pin "1") (pinfunction "1_1") (pintype "passive"))
      (node (ref "R35") (pin "1") (pinfunction "1_1") (pintype "passive"))
      (node (ref "R36") (pin "1") (pinfunction "1_1") (pintype "passive"))
    )
    (net (code "65") (name "Net-(IC1A--IN)") (class "Default")
      (node (ref "IC1") (pin "2") (pinfunction "-IN_2") (pintype "input"))
      (node (ref "R20") (pin "2") (pinfunction "2_2") (pintype "passive"))
      (node (ref "R37") (pin "1") (pinfunction "1_1") (pintype "passive"))
    )
    (net (code "66") (name "Net-(IC1A-OUT)") (class "Default")
      (node (ref "IC1") (pin "1") (pinfunction "OUT_1") (pintype "output"))
      (node (ref "R37") (pin "2") (pinfunction "2_2") (pintype "passive"))
      (node (ref "R38") (pin "1") (pinfunction "1_1") (pintype "passive"))
    )
    (net (code "67") (name "Net-(IC1B--IN)") (class "Default")
      (node (ref "IC1") (pin "6") (pinfunction "-IN_6") (pintype "input"))
      (node (ref "IC1") (pin "7") (pinfunction "OUT_7") (pintype "output"))
      (node (ref "R39") (pin "1") (pinfunction "1_1") (pintype "passive"))
    )
    (net (code "68") (name "Net-(JACK1-Pad1)") (class "Default")
      (node (ref "JACK1") (pin "1") (pinfunction "1_1") (pintype "passive"))
      (node (ref "R40") (pin "2") (pinfunction "2_2") (pintype "passive"))
    )
    (net (code "69") (name "Net-(JACK7-Pad1)") (class "Default")
      (node (ref "JACK7") (pin "1") (pinfunction "1_1") (pintype "passive"))
      (node (ref "R39") (pin "2") (pinfunction "2_2") (pintype "passive"))
    )
    (net (code "70") (name "Net-(R10A-A)") (class "Default")
      (node (ref "BRD1") (pin "AN0") (pinfunction "1_AN0") (pintype "passive"))
      (node (ref "BRD1") (pin "AN1") (pinfunction "1_AN1") (pintype "passive"))
      (node (ref "BRD1") (pin "AN2") (pinfunction "1_AN2") (pintype "passive"))
      (node (ref "BRD1") (pin "AN3") (pinfunction "1_AN3") (pintype "passive"))
      (node (ref "R1") (pin "SB") (pinfunction "A_SB") (pintype "passive"))
      (node (ref "R10") (pin "SB") (pinfunction "A_SB") (pintype "passive"))
      (node (ref "R11") (pin "SB") (pinfunction "A_SB") (pintype "passive"))
      (node (ref "R12") (pin "SB") (pinfunction "A_SB") (pintype "passive"))
      (node (ref "R13") (pin "SB") (pinfunction "A_SB") (pintype "passive"))
      (node (ref "R14") (pin "SB") (pinfunction "A_SB") (pintype "passive"))
      (node (ref "R15") (pin "SB") (pinfunction "A_SB") (pintype "passive"))
      (node (ref "R16") (pin "SB") (pinfunction "A_SB") (pintype "passive"))
      (node (ref "R2") (pin "SB") (pinfunction "A_SB") (pintype "passive"))
      (node (ref "R3") (pin "SB") (pinfunction "A_SB") (pintype "passive"))
      (node (ref "R4") (pin "SB") (pinfunction "A_SB") (pintype "passive"))
      (node (ref "R5") (pin "SB") (pinfunction "A_SB") (pintype "passive"))
      (node (ref "R6") (pin "SB") (pinfunction "A_SB") (pintype "passive"))
      (node (ref "R7") (pin "SB") (pinfunction "A_SB") (pintype "passive"))
      (node (ref "R8") (pin "SB") (pinfunction "A_SB") (pintype "passive"))
      (node (ref "R9") (pin "SB") (pinfunction "A_SB") (pintype "passive"))
    )
    (net (code "71") (name "Net-(SW1-P)") (class "Default")
      (node (ref "R21") (pin "2") (pinfunction "2_2") (pintype "passive"))
      (node (ref "SW1") (pin "C2") (pinfunction "P_C2") (pintype "passive"))
    )
    (net (code "72") (name "Net-(SW2-P)") (class "Default")
      (node (ref "R22") (pin "2") (pinfunction "2_2") (pintype "passive"))
      (node (ref "SW2") (pin "C2") (pinfunction "P_C2") (pintype "passive"))
    )
    (net (code "73") (name "Net-(SW3-P)") (class "Default")
      (node (ref "R23") (pin "2") (pinfunction "2_2") (pintype "passive"))
      (node (ref "SW3") (pin "C2") (pinfunction "P_C2") (pintype "passive"))
    )
    (net (code "74") (name "Net-(SW4-P)") (class "Default")
      (node (ref "R24") (pin "2") (pinfunction "2_2") (pintype "passive"))
      (node (ref "SW4") (pin "C2") (pinfunction "P_C2") (pintype "passive"))
    )
    (net (code "75") (name "Net-(SW5-P)") (class "Default")
      (node (ref "R25") (pin "2") (pinfunction "2_2") (pintype "passive"))
      (node (ref "SW5") (pin "C2") (pinfunction "P_C2") (pintype "passive"))
    )
    (net (code "76") (name "Net-(SW6-P)") (class "Default")
      (node (ref "R26") (pin "2") (pinfunction "2_2") (pintype "passive"))
      (node (ref "SW6") (pin "C2") (pinfunction "P_C2") (pintype "passive"))
    )
    (net (code "77") (name "Net-(SW7-P)") (class "Default")
      (node (ref "R27") (pin "2") (pinfunction "2_2") (pintype "passive"))
      (node (ref "SW7") (pin "C2") (pinfunction "P_C2") (pintype "passive"))
    )
    (net (code "78") (name "Net-(SW8-P)") (class "Default")
      (node (ref "R28") (pin "2") (pinfunction "2_2") (pintype "passive"))
      (node (ref "SW8") (pin "C2") (pinfunction "P_C2") (pintype "passive"))
    )
    (net (code "79") (name "Net-(SW9-P)") (class "Default")
      (node (ref "R29") (pin "2") (pinfunction "2_2") (pintype "passive"))
      (node (ref "SW9") (pin "C2") (pinfunction "P_C2") (pintype "passive"))
    )
    (net (code "80") (name "Net-(SW10-P)") (class "Default")
      (node (ref "R30") (pin "2") (pinfunction "2_2") (pintype "passive"))
      (node (ref "SW10") (pin "C2") (pinfunction "P_C2") (pintype "passive"))
    )
    (net (code "81") (name "Net-(SW11-P)") (class "Default")
      (node (ref "R31") (pin "2") (pinfunction "2_2") (pintype "passive"))
      (node (ref "SW11") (pin "C2") (pinfunction "P_C2") (pintype "passive"))
    )
    (net (code "82") (name "Net-(SW12-P)") (class "Default")
      (node (ref "R32") (pin "2") (pinfunction "2_2") (pintype "passive"))
      (node (ref "SW12") (pin "C2") (pinfunction "P_C2") (pintype "passive"))
    )
    (net (code "83") (name "Net-(SW13-P)") (class "Default")
      (node (ref "R33") (pin "2") (pinfunction "2_2") (pintype "passive"))
      (node (ref "SW13") (pin "C2") (pinfunction "P_C2") (pintype "passive"))
    )
    (net (code "84") (name "Net-(SW14-P)") (class "Default")
      (node (ref "R34") (pin "2") (pinfunction "2_2") (pintype "passive"))
      (node (ref "SW14") (pin "C2") (pinfunction "P_C2") (pintype "passive"))
    )
    (net (code "85") (name "Net-(SW15-P)") (class "Default")
      (node (ref "R35") (pin "2") (pinfunction "2_2") (pintype "passive"))
      (node (ref "SW15") (pin "C2") (pinfunction "P_C2") (pintype "passive"))
    )
    (net (code "86") (name "Net-(SW16-P)") (class "Default")
      (node (ref "R36") (pin "2") (pinfunction "2_2") (pintype "passive"))
      (node (ref "SW16") (pin "C2") (pinfunction "P_C2") (pintype "passive"))
    )
    (net (code "87") (name "unconnected-(SW1-S-PadC3)") (class "Default")
      (node (ref "SW1") (pin "C3") (pinfunction "S_C3") (pintype "passive"))
    )
    (net (code "88") (name "unconnected-(SW2-S-PadC3)") (class "Default")
      (node (ref "SW2") (pin "C3") (pinfunction "S_C3") (pintype "passive"))
    )
    (net (code "89") (name "unconnected-(SW3-S-PadC3)") (class "Default")
      (node (ref "SW3") (pin "C3") (pinfunction "S_C3") (pintype "passive"))
    )
    (net (code "90") (name "unconnected-(SW4-S-PadC3)") (class "Default")
      (node (ref "SW4") (pin "C3") (pinfunction "S_C3") (pintype "passive"))
    )
    (net (code "91") (name "unconnected-(SW5-S-PadC3)") (class "Default")
      (node (ref "SW5") (pin "C3") (pinfunction "S_C3") (pintype "passive"))
    )
    (net (code "92") (name "unconnected-(SW6-S-PadC3)") (class "Default")
      (node (ref "SW6") (pin "C3") (pinfunction "S_C3") (pintype "passive"))
    )
    (net (code "93") (name "unconnected-(SW7-S-PadC3)") (class "Default")
      (node (ref "SW7") (pin "C3") (pinfunction "S_C3") (pintype "passive"))
    )
    (net (code "94") (name "unconnected-(SW8-S-PadC3)") (class "Default")
      (node (ref "SW8") (pin "C3") (pinfunction "S_C3") (pintype "passive"))
    )
    (net (code "95") (name "unconnected-(SW9-S-PadC3)") (class "Default")
      (node (ref "SW9") (pin "C3") (pinfunction "S_C3") (pintype "passive"))
    )
    (net (code "96") (name "unconnected-(SW10-S-PadC3)") (class "Default")
      (node (ref "SW10") (pin "C3") (pinfunction "S_C3") (pintype "passive"))
    )
    (net (code "97") (name "unconnected-(SW11-S-PadC3)") (class "Default")
      (node (ref "SW11") (pin "C3") (pinfunction "S_C3") (pintype "passive"))
    )
    (net (code "98") (name "unconnected-(SW12-S-PadC3)") (class "Default")
      (node (ref "SW12") (pin "C3") (pinfunction "S_C3") (pintype "passive"))
    )
    (net (code "99") (name "unconnected-(SW13-S-PadC3)") (class "Default")
      (node (ref "SW13") (pin "C3") (pinfunction "S_C3") (pintype "passive"))
    )
    (net (code "100") (name "unconnected-(SW14-S-PadC3)") (class "Default")
      (node (ref "SW14") (pin "C3") (pinfunction "S_C3") (pintype "passive"))
    )
    (net (code "101") (name "unconnected-(SW15-S-PadC3)") (class "Default")
      (node (ref "SW15") (pin "C3") (pinfunction "S_C3") (pintype "passive"))
    )
    (net (code "102") (name "unconnected-(SW16-S-PadC3)") (class "Default")
      (node (ref "SW16") (pin "C3") (pinfunction "S_C3") (pintype "passive"))
    )
    (net (code "103") (name "unconnected-(SW17-O-PadC1)") (class "Default")
      (node (ref "SW17") (pin "C1") (pinfunction "O_C1") (pintype "passive"))
    )
  )
)
